# CC3000_Breakout.net
KiCad netlist of a schematic drawn in EAGLE
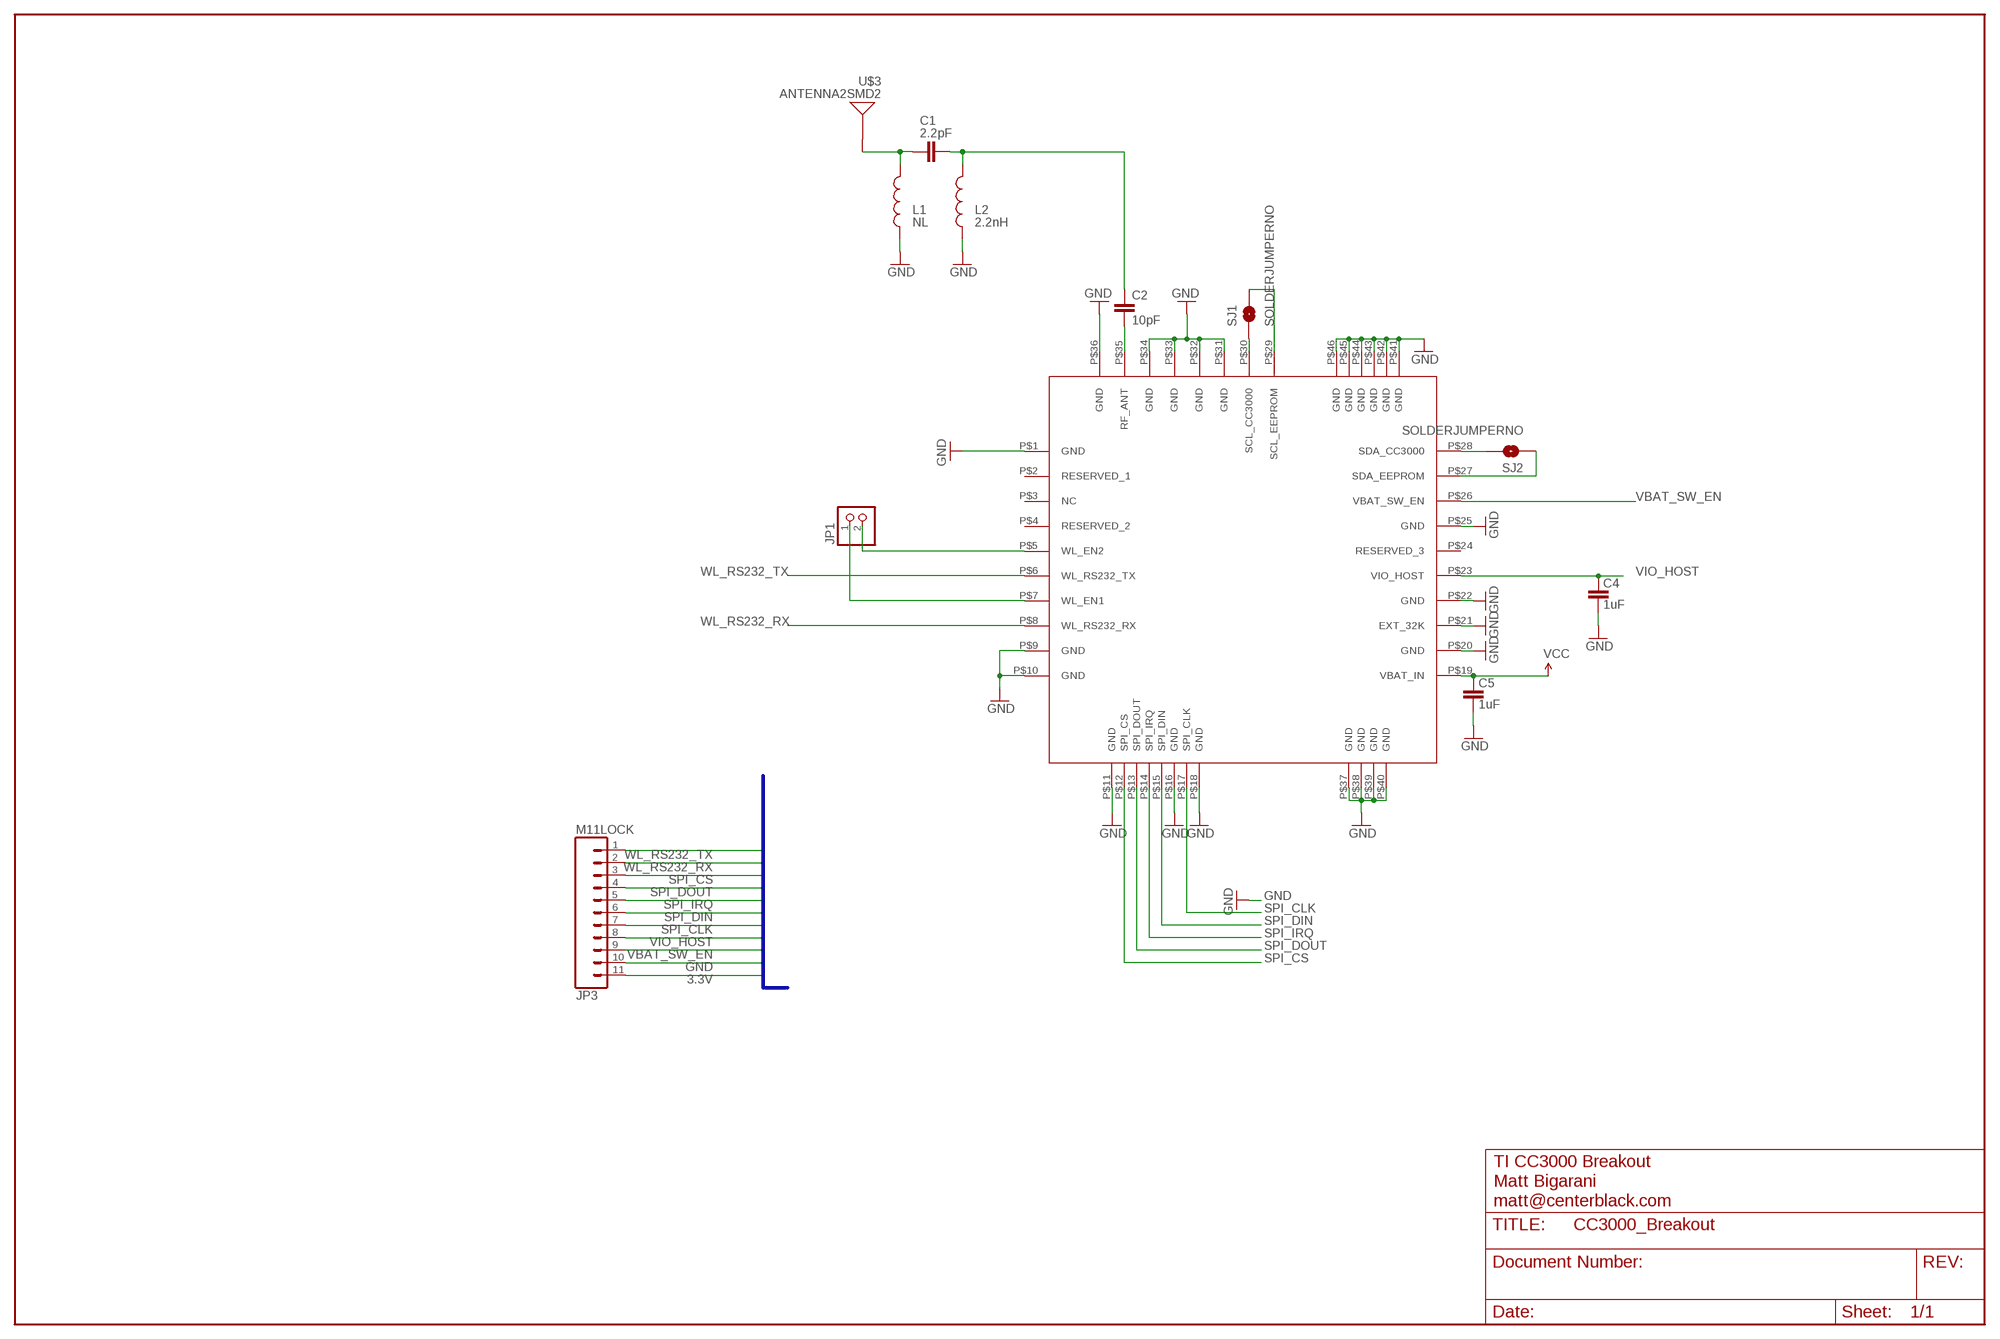
[diagram p0: schematic, sheet 1]

(export (version "E")
  (design (tool "Eeschema 10.0.6"))
  (components
    (comp (ref "C1")
      (value "2.2pF")
      (footprint "eagle-import:0805")
      (libsource (lib "eagle-import") (part "CAP0805"))
    )
    (comp (ref "C2")
      (value "10pF")
      (footprint "eagle-import:0805")
      (libsource (lib "eagle-import") (part "CAP0805"))
    )
    (comp (ref "C4")
      (value "1uF")
      (footprint "eagle-import:0805")
      (libsource (lib "eagle-import") (part "CAP0805"))
    )
    (comp (ref "C5")
      (value "1uF")
      (footprint "eagle-import:0805")
      (libsource (lib "eagle-import") (part "CAP0805"))
    )
    (comp (ref "JP1")
      (value "PINHD-1X2")
      (footprint "eagle-import:1X02")
      (libsource (lib "eagle-import") (part "PINHD-1X2"))
    )
    (comp (ref "JP3")
      (value "M11LOCK")
      (footprint "eagle-import:1X11_LOCK")
      (libsource (lib "eagle-import") (part "M11LOCK"))
    )
    (comp (ref "L1")
      (value "NL")
      (footprint "eagle-import:0805")
      (libsource (lib "eagle-import") (part "INDUCTOR0805"))
    )
    (comp (ref "L2")
      (value "2.2nH")
      (footprint "eagle-import:0805")
      (libsource (lib "eagle-import") (part "INDUCTOR0805"))
    )
    (comp (ref "SJ1")
      (value "SOLDERJUMPERNO")
      (footprint "eagle-import:SJ_2S-NO")
      (libsource (lib "eagle-import") (part "SOLDERJUMPERNO"))
    )
    (comp (ref "SJ2")
      (value "SOLDERJUMPERNO")
      (footprint "eagle-import:SJ_2S-NO")
      (libsource (lib "eagle-import") (part "SOLDERJUMPERNO"))
    )
    (comp (ref "U$1")
      (value "CC3000")
      (footprint "eagle-import:CC3000")
      (fields (field (name "AUTHOR") "Matt Bigarani"))
      (libsource (lib "eagle-import") (part "CC3000"))
    )
    (comp (ref "U$3")
      (value "ANTENNA2SMD2")
      (footprint "eagle-import:ANTENNA-CHIP3")
      (libsource (lib "eagle-import") (part "ANTENNA2SMD2"))
    )
  )
  (nets
    (net (code "1") (name "/SPI_CLK") (class "Default")
      (node (ref "JP3") (pin "7") (pinfunction "7_7") (pintype "passive"))
      (node (ref "U$1") (pin "P$17") (pinfunction "SPI_CLK_P$17") (pintype "bidirectional"))
    )
    (net (code "2") (name "/SPI_CS") (class "Default")
      (node (ref "JP3") (pin "3") (pinfunction "3_3") (pintype "passive"))
      (node (ref "U$1") (pin "P$12") (pinfunction "SPI_CS_P$12") (pintype "bidirectional"))
    )
    (net (code "3") (name "/SPI_DIN") (class "Default")
      (node (ref "JP3") (pin "6") (pinfunction "6_6") (pintype "passive"))
      (node (ref "U$1") (pin "P$15") (pinfunction "SPI_DIN_P$15") (pintype "bidirectional"))
    )
    (net (code "4") (name "/SPI_DOUT") (class "Default")
      (node (ref "JP3") (pin "4") (pinfunction "4_4") (pintype "passive"))
      (node (ref "U$1") (pin "P$13") (pinfunction "SPI_DOUT_P$13") (pintype "bidirectional"))
    )
    (net (code "5") (name "/SPI_IRQ") (class "Default")
      (node (ref "JP3") (pin "5") (pinfunction "5_5") (pintype "passive"))
      (node (ref "U$1") (pin "P$14") (pinfunction "SPI_IRQ_P$14") (pintype "bidirectional"))
    )
    (net (code "6") (name "/VBAT_SW_EN") (class "Default")
      (node (ref "JP3") (pin "9") (pinfunction "9_9") (pintype "passive"))
      (node (ref "U$1") (pin "P$26") (pinfunction "VBAT_SW_EN_P$26") (pintype "bidirectional"))
    )
    (net (code "7") (name "/VIO_HOST") (class "Default")
      (node (ref "C4") (pin "2") (pinfunction "2_2") (pintype "passive"))
      (node (ref "JP3") (pin "8") (pinfunction "8_8") (pintype "passive"))
      (node (ref "U$1") (pin "P$23") (pinfunction "VIO_HOST_P$23") (pintype "bidirectional"))
    )
    (net (code "8") (name "/WL_RS232_RX") (class "Default")
      (node (ref "JP3") (pin "2") (pinfunction "2_2") (pintype "passive"))
      (node (ref "U$1") (pin "P$8") (pinfunction "WL_RS232_RX_P$8") (pintype "bidirectional"))
    )
    (net (code "9") (name "/WL_RS232_TX") (class "Default")
      (node (ref "JP3") (pin "1") (pinfunction "1_1") (pintype "passive"))
      (node (ref "U$1") (pin "P$6") (pinfunction "WL_RS232_TX_P$6") (pintype "bidirectional"))
    )
    (net (code "10") (name "GND") (class "Default")
      (node (ref "C4") (pin "1") (pinfunction "1_1") (pintype "passive"))
      (node (ref "C5") (pin "1") (pinfunction "1_1") (pintype "passive"))
      (node (ref "JP3") (pin "10") (pinfunction "10_10") (pintype "passive"))
      (node (ref "L1") (pin "1") (pinfunction "1_1") (pintype "passive"))
      (node (ref "L2") (pin "1") (pinfunction "1_1") (pintype "passive"))
      (node (ref "U$1") (pin "P$1") (pinfunction "GND_P$1") (pintype "power_in"))
      (node (ref "U$1") (pin "P$10") (pinfunction "GND_P$10") (pintype "power_in"))
      (node (ref "U$1") (pin "P$11") (pinfunction "GND_P$11") (pintype "power_in"))
      (node (ref "U$1") (pin "P$16") (pinfunction "GND_P$16") (pintype "power_in"))
      (node (ref "U$1") (pin "P$18") (pinfunction "GND_P$18") (pintype "power_in"))
      (node (ref "U$1") (pin "P$20") (pinfunction "GND_P$20") (pintype "bidirectional"))
      (node (ref "U$1") (pin "P$21") (pinfunction "EXT_32K_P$21") (pintype "bidirectional"))
      (node (ref "U$1") (pin "P$22") (pinfunction "GND_P$22") (pintype "bidirectional"))
      (node (ref "U$1") (pin "P$25") (pinfunction "GND_P$25") (pintype "bidirectional"))
      (node (ref "U$1") (pin "P$31") (pinfunction "GND_P$31") (pintype "power_in"))
      (node (ref "U$1") (pin "P$32") (pinfunction "GND_P$32") (pintype "power_in"))
      (node (ref "U$1") (pin "P$33") (pinfunction "GND_P$33") (pintype "power_in"))
      (node (ref "U$1") (pin "P$34") (pinfunction "GND_P$34") (pintype "power_in"))
      (node (ref "U$1") (pin "P$36") (pinfunction "GND_P$36") (pintype "passive"))
      (node (ref "U$1") (pin "P$37") (pinfunction "GND_P$37") (pintype "power_in"))
      (node (ref "U$1") (pin "P$38") (pinfunction "GND_P$38") (pintype "passive"))
      (node (ref "U$1") (pin "P$39") (pinfunction "GND_P$39") (pintype "power_in"))
      (node (ref "U$1") (pin "P$40") (pinfunction "GND_P$40") (pintype "power_in"))
      (node (ref "U$1") (pin "P$41") (pinfunction "GND_P$41") (pintype "power_in"))
      (node (ref "U$1") (pin "P$42") (pinfunction "GND_P$42") (pintype "power_in"))
      (node (ref "U$1") (pin "P$43") (pinfunction "GND_P$43") (pintype "power_in"))
      (node (ref "U$1") (pin "P$44") (pinfunction "GND_P$44") (pintype "power_in"))
      (node (ref "U$1") (pin "P$45") (pinfunction "GND_P$45") (pintype "power_in"))
      (node (ref "U$1") (pin "P$46") (pinfunction "GND_P$46") (pintype "power_in"))
      (node (ref "U$1") (pin "P$9") (pinfunction "GND_P$9") (pintype "bidirectional"))
    )
    (net (code "11") (name "Net-(C1-Pad2)") (class "Default")
      (node (ref "C1") (pin "2") (pinfunction "2_2") (pintype "passive"))
      (node (ref "C2") (pin "1") (pinfunction "1_1") (pintype "passive"))
      (node (ref "L2") (pin "2") (pinfunction "2_2") (pintype "passive"))
    )
    (net (code "12") (name "Net-(U$1-RF_ANT)") (class "Default")
      (node (ref "C2") (pin "2") (pinfunction "2_2") (pintype "passive"))
      (node (ref "U$1") (pin "P$35") (pinfunction "RF_ANT_P$35") (pintype "bidirectional"))
    )
    (net (code "13") (name "Net-(U$1-SCL_CC3000)") (class "Default")
      (node (ref "SJ1") (pin "1") (pinfunction "1_1") (pintype "passive"))
      (node (ref "U$1") (pin "P$30") (pinfunction "SCL_CC3000_P$30") (pintype "power_in"))
    )
    (net (code "14") (name "Net-(U$1-SCL_EEPROM)") (class "Default")
      (node (ref "SJ1") (pin "2") (pinfunction "2_2") (pintype "passive"))
      (node (ref "U$1") (pin "P$29") (pinfunction "SCL_EEPROM_P$29") (pintype "power_in"))
    )
    (net (code "15") (name "Net-(U$1-SDA_CC3000)") (class "Default")
      (node (ref "SJ2") (pin "2") (pinfunction "2_2") (pintype "passive"))
      (node (ref "U$1") (pin "P$28") (pinfunction "SDA_CC3000_P$28") (pintype "bidirectional"))
    )
    (net (code "16") (name "Net-(U$1-SDA_EEPROM)") (class "Default")
      (node (ref "SJ2") (pin "1") (pinfunction "1_1") (pintype "passive"))
      (node (ref "U$1") (pin "P$27") (pinfunction "SDA_EEPROM_P$27") (pintype "bidirectional"))
    )
    (net (code "17") (name "Net-(U$1-WL_EN1)") (class "Default")
      (node (ref "JP1") (pin "1") (pinfunction "1_1") (pintype "passive"))
      (node (ref "U$1") (pin "P$7") (pinfunction "WL_EN1_P$7") (pintype "bidirectional"))
    )
    (net (code "18") (name "Net-(U$1-WL_EN2)") (class "Default")
      (node (ref "JP1") (pin "2") (pinfunction "2_2") (pintype "passive"))
      (node (ref "U$1") (pin "P$5") (pinfunction "WL_EN2_P$5") (pintype "bidirectional"))
    )
    (net (code "19") (name "Net-(U$3-SIGNAL)") (class "Default")
      (node (ref "C1") (pin "1") (pinfunction "1_1") (pintype "passive"))
      (node (ref "L1") (pin "2") (pinfunction "2_2") (pintype "passive"))
      (node (ref "U$3") (pin "FEED") (pinfunction "SIGNAL_FEED") (pintype "bidirectional"))
    )
    (net (code "20") (name "VCC") (class "Default")
      (node (ref "C5") (pin "2") (pinfunction "2_2") (pintype "passive"))
      (node (ref "JP3") (pin "11") (pinfunction "11_11") (pintype "passive"))
      (node (ref "U$1") (pin "P$19") (pinfunction "VBAT_IN_P$19") (pintype "bidirectional"))
    )
    (net (code "21") (name "unconnected-(U$1-NC-PadP$3)") (class "Default")
      (node (ref "U$1") (pin "P$3") (pinfunction "NC_P$3") (pintype "no_connect"))
    )
    (net (code "22") (name "unconnected-(U$1-RESERVED_1-PadP$2)") (class "Default")
      (node (ref "U$1") (pin "P$2") (pinfunction "RESERVED_1_P$2") (pintype "bidirectional"))
    )
    (net (code "23") (name "unconnected-(U$1-RESERVED_2-PadP$4)") (class "Default")
      (node (ref "U$1") (pin "P$4") (pinfunction "RESERVED_2_P$4") (pintype "bidirectional"))
    )
    (net (code "24") (name "unconnected-(U$1-RESERVED_3-PadP$24)") (class "Default")
      (node (ref "U$1") (pin "P$24") (pinfunction "RESERVED_3_P$24") (pintype "bidirectional"))
    )
  )
)
